# input_stage.net
KiCad netlist of a schematic drawn in EAGLE
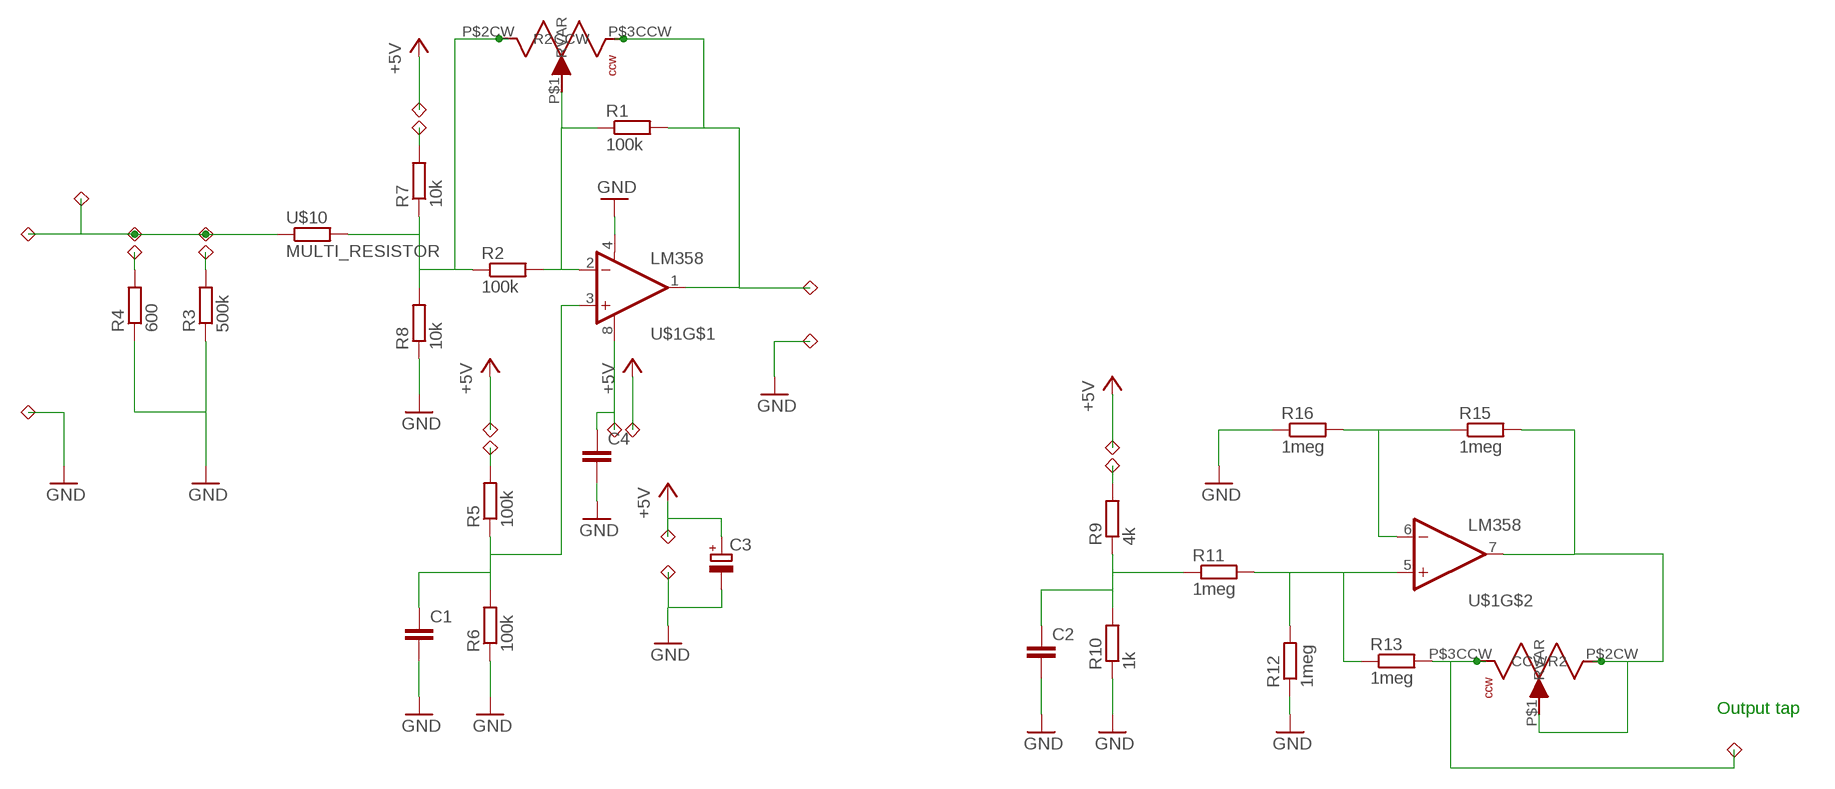
[diagram p0: schematic, sheet 1]

(export (version "E")
  (design (tool "Eeschema 10.0.6"))
  (components
    (comp (ref "C1")
      (value "C-EUC0603")
      (footprint "eagle-import:C0603")
      (libsource (lib "eagle-import") (part "C-EUC0603"))
    )
    (comp (ref "C2")
      (value "C-EUC0603")
      (footprint "eagle-import:C0603")
      (libsource (lib "eagle-import") (part "C-EUC0603"))
    )
    (comp (ref "C3")
      (value "CPOL-EUC/6032-28R")
      (footprint "eagle-import:C_6032-28R")
      (libsource (lib "eagle-import") (part "CPOL-EUC/6032-28R"))
    )
    (comp (ref "C4")
      (value "C-EUC0603")
      (footprint "eagle-import:C0603")
      (libsource (lib "eagle-import") (part "C-EUC0603"))
    )
    (comp (ref "R1")
      (value "100k")
      (footprint "eagle-import:R0603")
      (libsource (lib "eagle-import") (part "R-EU_R0603"))
    )
    (comp (ref "R2")
      (value "100k")
      (footprint "eagle-import:R0603")
      (libsource (lib "eagle-import") (part "R-EU_R0603"))
    )
    (comp (ref "R3")
      (value "500k")
      (footprint "eagle-import:R0603")
      (libsource (lib "eagle-import") (part "R-EU_R0603"))
    )
    (comp (ref "R4")
      (value "600")
      (footprint "eagle-import:R0603")
      (libsource (lib "eagle-import") (part "R-EU_R0603"))
    )
    (comp (ref "R5")
      (value "100k")
      (footprint "eagle-import:R0603")
      (libsource (lib "eagle-import") (part "R-EU_R0603"))
    )
    (comp (ref "R6")
      (value "100k")
      (footprint "eagle-import:R0603")
      (libsource (lib "eagle-import") (part "R-EU_R0603"))
    )
    (comp (ref "R7")
      (value "10k")
      (footprint "eagle-import:R0603")
      (libsource (lib "eagle-import") (part "R-EU_R0603"))
    )
    (comp (ref "R8")
      (value "10k")
      (footprint "eagle-import:R0603")
      (libsource (lib "eagle-import") (part "R-EU_R0603"))
    )
    (comp (ref "R9")
      (value "4k")
      (footprint "eagle-import:R0603")
      (libsource (lib "eagle-import") (part "R-EU_R0603"))
    )
    (comp (ref "R10")
      (value "1k")
      (footprint "eagle-import:R0603")
      (libsource (lib "eagle-import") (part "R-EU_R0603"))
    )
    (comp (ref "R11")
      (value "1meg")
      (footprint "eagle-import:R0603")
      (libsource (lib "eagle-import") (part "R-EU_R0603"))
    )
    (comp (ref "R12")
      (value "1meg")
      (footprint "eagle-import:R0603")
      (libsource (lib "eagle-import") (part "R-EU_R0603"))
    )
    (comp (ref "R13")
      (value "1meg")
      (footprint "eagle-import:R0603")
      (libsource (lib "eagle-import") (part "R-EU_R0603"))
    )
    (comp (ref "R15")
      (value "1meg")
      (footprint "eagle-import:R0603")
      (libsource (lib "eagle-import") (part "R-EU_R0603"))
    )
    (comp (ref "R16")
      (value "1meg")
      (footprint "eagle-import:R0603")
      (libsource (lib "eagle-import") (part "R-EU_R0603"))
    )
    (comp (ref "U$1")
      (value "LM358")
      (footprint "eagle-import:SO08")
      (libsource (lib "eagle-import") (part "LM358"))
    )
    (comp (ref "U$2")
      (value "1PIN")
      (footprint "eagle-import:THUMBNAIL")
      (libsource (lib "eagle-import") (part "1PIN"))
    )
    (comp (ref "U$3")
      (value "1PIN")
      (footprint "eagle-import:THUMBNAIL")
      (libsource (lib "eagle-import") (part "1PIN"))
    )
    (comp (ref "U$4")
      (value "1PIN")
      (footprint "eagle-import:THUMBNAIL")
      (libsource (lib "eagle-import") (part "1PIN"))
    )
    (comp (ref "U$5")
      (value "1PIN")
      (footprint "eagle-import:THUMBNAIL")
      (libsource (lib "eagle-import") (part "1PIN"))
    )
    (comp (ref "U$6")
      (value "1PIN")
      (footprint "eagle-import:THUMBNAIL")
      (libsource (lib "eagle-import") (part "1PIN"))
    )
    (comp (ref "U$7")
      (value "1PIN")
      (footprint "eagle-import:THUMBNAIL")
      (libsource (lib "eagle-import") (part "1PIN"))
    )
    (comp (ref "U$8")
      (value "1PIN")
      (footprint "eagle-import:THUMBNAIL")
      (libsource (lib "eagle-import") (part "1PIN"))
    )
    (comp (ref "U$9")
      (value "1PIN")
      (footprint "eagle-import:THUMBNAIL")
      (libsource (lib "eagle-import") (part "1PIN"))
    )
    (comp (ref "U$10")
      (value "MULTI_RESISTOR")
      (footprint "eagle-import:MULTI_PAD")
      (libsource (lib "eagle-import") (part "MULTI_RESISTOR"))
    )
    (comp (ref "U$11")
      (value "1PIN")
      (footprint "eagle-import:THUMBNAIL")
      (libsource (lib "eagle-import") (part "1PIN"))
    )
    (comp (ref "U$12")
      (value "1PIN")
      (footprint "eagle-import:THUMBNAIL")
      (libsource (lib "eagle-import") (part "1PIN"))
    )
    (comp (ref "U$13")
      (value "1PIN")
      (footprint "eagle-import:THUMBNAIL")
      (libsource (lib "eagle-import") (part "1PIN"))
    )
    (comp (ref "U$14")
      (value "1PIN")
      (footprint "eagle-import:THUMBNAIL")
      (libsource (lib "eagle-import") (part "1PIN"))
    )
    (comp (ref "U$15")
      (value "SMD-POT")
      (footprint "eagle-import:POT_PADS")
      (libsource (lib "eagle-import") (part "SMD-POT"))
    )
    (comp (ref "U$16")
      (value "1PIN_SM")
      (footprint "eagle-import:THUMBNAIL_SM")
      (libsource (lib "eagle-import") (part "1PIN_SM"))
    )
    (comp (ref "U$17")
      (value "1PIN_SM")
      (footprint "eagle-import:THUMBNAIL_SM")
      (libsource (lib "eagle-import") (part "1PIN_SM"))
    )
    (comp (ref "U$18")
      (value "1PIN_SM")
      (footprint "eagle-import:THUMBNAIL_SM")
      (libsource (lib "eagle-import") (part "1PIN_SM"))
    )
    (comp (ref "U$19")
      (value "1PIN_SM")
      (footprint "eagle-import:THUMBNAIL_SM")
      (libsource (lib "eagle-import") (part "1PIN_SM"))
    )
    (comp (ref "U$20")
      (value "1PIN_SM")
      (footprint "eagle-import:THUMBNAIL_SM")
      (libsource (lib "eagle-import") (part "1PIN_SM"))
    )
    (comp (ref "U$21")
      (value "1PIN_SM")
      (footprint "eagle-import:THUMBNAIL_SM")
      (libsource (lib "eagle-import") (part "1PIN_SM"))
    )
    (comp (ref "U$22")
      (value "1PIN_SM")
      (footprint "eagle-import:THUMBNAIL_SM")
      (libsource (lib "eagle-import") (part "1PIN_SM"))
    )
    (comp (ref "U$23")
      (value "1PIN_SM")
      (footprint "eagle-import:THUMBNAIL_SM")
      (libsource (lib "eagle-import") (part "1PIN_SM"))
    )
    (comp (ref "U$24")
      (value "SMD-POT")
      (footprint "eagle-import:POT_PADS")
      (libsource (lib "eagle-import") (part "SMD-POT"))
    )
  )
  (nets
    (net (code "1") (name "+5V") (class "Default")
      (node (ref "C3") (pin "+") (pinfunction "+_+") (pintype "passive"))
      (node (ref "U$17") (pin "P$1") (pinfunction "P$1_P$1") (pintype "bidirectional"))
      (node (ref "U$19") (pin "P$1") (pinfunction "P$1_P$1") (pintype "bidirectional"))
      (node (ref "U$2") (pin "P$1") (pinfunction "P$1_P$1") (pintype "bidirectional"))
      (node (ref "U$21") (pin "P$1") (pinfunction "P$1_P$1") (pintype "bidirectional"))
      (node (ref "U$23") (pin "P$1") (pinfunction "P$1_P$1") (pintype "bidirectional"))
    )
    (net (code "2") (name "GND") (class "Default")
      (node (ref "C1") (pin "2") (pinfunction "2_2") (pintype "passive"))
      (node (ref "C2") (pin "2") (pinfunction "2_2") (pintype "passive"))
      (node (ref "C3") (pin "-") (pinfunction "-_-") (pintype "passive"))
      (node (ref "C4") (pin "2") (pinfunction "2_2") (pintype "passive"))
      (node (ref "R10") (pin "1") (pinfunction "1_1") (pintype "passive"))
      (node (ref "R12") (pin "1") (pinfunction "1_1") (pintype "passive"))
      (node (ref "R16") (pin "1") (pinfunction "1_1") (pintype "passive"))
      (node (ref "R3") (pin "1") (pinfunction "1_1") (pintype "passive"))
      (node (ref "R4") (pin "1") (pinfunction "1_1") (pintype "passive"))
      (node (ref "R6") (pin "1") (pinfunction "1_1") (pintype "passive"))
      (node (ref "R8") (pin "1") (pinfunction "1_1") (pintype "passive"))
      (node (ref "U$1") (pin "4") (pinfunction "V-_4") (pintype "power_in"))
      (node (ref "U$3") (pin "P$1") (pinfunction "P$1_P$1") (pintype "bidirectional"))
      (node (ref "U$8") (pin "P$1") (pinfunction "P$1_P$1") (pintype "bidirectional"))
      (node (ref "U$9") (pin "P$1") (pinfunction "P$1_P$1") (pintype "bidirectional"))
    )
    (net (code "3") (name "Net-(C2-Pad1)") (class "Default")
      (node (ref "C2") (pin "1") (pinfunction "1_1") (pintype "passive"))
      (node (ref "R10") (pin "2") (pinfunction "2_2") (pintype "passive"))
      (node (ref "R11") (pin "1") (pinfunction "1_1") (pintype "passive"))
      (node (ref "R9") (pin "1") (pinfunction "1_1") (pintype "passive"))
    )
    (net (code "4") (name "Net-(R3-Pad2)") (class "Default")
      (node (ref "R3") (pin "2") (pinfunction "2_2") (pintype "passive"))
      (node (ref "U$11") (pin "P$1") (pinfunction "P$1_P$1") (pintype "bidirectional"))
    )
    (net (code "5") (name "Net-(R4-Pad2)") (class "Default")
      (node (ref "R4") (pin "2") (pinfunction "2_2") (pintype "passive"))
      (node (ref "U$7") (pin "P$1") (pinfunction "P$1_P$1") (pintype "bidirectional"))
    )
    (net (code "6") (name "Net-(R5-Pad2)") (class "Default")
      (node (ref "R5") (pin "2") (pinfunction "2_2") (pintype "passive"))
      (node (ref "U$20") (pin "P$1") (pinfunction "P$1_P$1") (pintype "bidirectional"))
    )
    (net (code "7") (name "Net-(R7-Pad2)") (class "Default")
      (node (ref "R7") (pin "2") (pinfunction "2_2") (pintype "passive"))
      (node (ref "U$18") (pin "P$1") (pinfunction "P$1_P$1") (pintype "bidirectional"))
    )
    (net (code "8") (name "Net-(R9-Pad2)") (class "Default")
      (node (ref "R9") (pin "2") (pinfunction "2_2") (pintype "passive"))
      (node (ref "U$16") (pin "P$1") (pinfunction "P$1_P$1") (pintype "bidirectional"))
    )
    (net (code "9") (name "Net-(U$1A-+IN)") (class "Default")
      (node (ref "C1") (pin "1") (pinfunction "1_1") (pintype "passive"))
      (node (ref "R5") (pin "1") (pinfunction "1_1") (pintype "passive"))
      (node (ref "R6") (pin "2") (pinfunction "2_2") (pintype "passive"))
      (node (ref "U$1") (pin "3") (pinfunction "+IN_3") (pintype "input"))
    )
    (net (code "10") (name "Net-(U$1A--IN)") (class "Default")
      (node (ref "R1") (pin "1") (pinfunction "1_1") (pintype "passive"))
      (node (ref "R2") (pin "2") (pinfunction "2_2") (pintype "passive"))
      (node (ref "U$1") (pin "2") (pinfunction "-IN_2") (pintype "input"))
      (node (ref "U$24") (pin "P$1") (pinfunction "RVAR_P$1") (pintype "bidirectional"))
    )
    (net (code "11") (name "Net-(U$1A-OUT)") (class "Default")
      (node (ref "R1") (pin "2") (pinfunction "2_2") (pintype "passive"))
      (node (ref "U$1") (pin "1") (pinfunction "OUT_1") (pintype "output"))
      (node (ref "U$24") (pin "P$3CCW") (pinfunction "CCW_P$3CCW") (pintype "bidirectional"))
      (node (ref "U$4") (pin "P$1") (pinfunction "P$1_P$1") (pintype "bidirectional"))
    )
    (net (code "12") (name "Net-(U$1A-V+)") (class "Default")
      (node (ref "C4") (pin "1") (pinfunction "1_1") (pintype "passive"))
      (node (ref "U$1") (pin "8") (pinfunction "V+_8") (pintype "power_in"))
      (node (ref "U$22") (pin "P$1") (pinfunction "P$1_P$1") (pintype "bidirectional"))
    )
    (net (code "13") (name "Net-(U$1B-+IN)") (class "Default")
      (node (ref "R11") (pin "2") (pinfunction "2_2") (pintype "passive"))
      (node (ref "R12") (pin "2") (pinfunction "2_2") (pintype "passive"))
      (node (ref "R13") (pin "1") (pinfunction "1_1") (pintype "passive"))
      (node (ref "U$1") (pin "5") (pinfunction "+IN_5") (pintype "input"))
    )
    (net (code "14") (name "Net-(U$1B--IN)") (class "Default")
      (node (ref "R15") (pin "1") (pinfunction "1_1") (pintype "passive"))
      (node (ref "R16") (pin "2") (pinfunction "2_2") (pintype "passive"))
      (node (ref "U$1") (pin "6") (pinfunction "-IN_6") (pintype "input"))
    )
    (net (code "15") (name "Net-(U$10-Pad1)") (class "Default")
      (node (ref "U$10") (pin "1") (pinfunction "1_1") (pintype "passive"))
      (node (ref "U$12") (pin "P$1") (pinfunction "P$1_P$1") (pintype "bidirectional"))
      (node (ref "U$13") (pin "P$1") (pinfunction "P$1_P$1") (pintype "bidirectional"))
      (node (ref "U$5") (pin "P$1") (pinfunction "P$1_P$1") (pintype "bidirectional"))
      (node (ref "U$6") (pin "P$1") (pinfunction "P$1_P$1") (pintype "bidirectional"))
    )
    (net (code "16") (name "Net-(U$15-CCW)") (class "Default")
      (node (ref "R13") (pin "2") (pinfunction "2_2") (pintype "passive"))
      (node (ref "U$14") (pin "P$1") (pinfunction "P$1_P$1") (pintype "bidirectional"))
      (node (ref "U$15") (pin "P$3CCW") (pinfunction "CCW_P$3CCW") (pintype "bidirectional"))
    )
    (net (code "17") (name "Net-(U$15-R2)") (class "Default")
      (node (ref "R15") (pin "2") (pinfunction "2_2") (pintype "passive"))
      (node (ref "U$1") (pin "7") (pinfunction "OUT_7") (pintype "output"))
      (node (ref "U$15") (pin "P$1") (pinfunction "RVAR_P$1") (pintype "bidirectional"))
      (node (ref "U$15") (pin "P$2CW") (pinfunction "R2_P$2CW") (pintype "bidirectional"))
    )
    (net (code "18") (name "Net-(U$24-R2)") (class "Default")
      (node (ref "R2") (pin "1") (pinfunction "1_1") (pintype "passive"))
      (node (ref "R7") (pin "1") (pinfunction "1_1") (pintype "passive"))
      (node (ref "R8") (pin "2") (pinfunction "2_2") (pintype "passive"))
      (node (ref "U$10") (pin "2") (pinfunction "2_2") (pintype "passive"))
      (node (ref "U$24") (pin "P$2CW") (pinfunction "R2_P$2CW") (pintype "bidirectional"))
    )
  )
)
